# bluebox.net
KiCad netlist of a schematic drawn in EAGLE
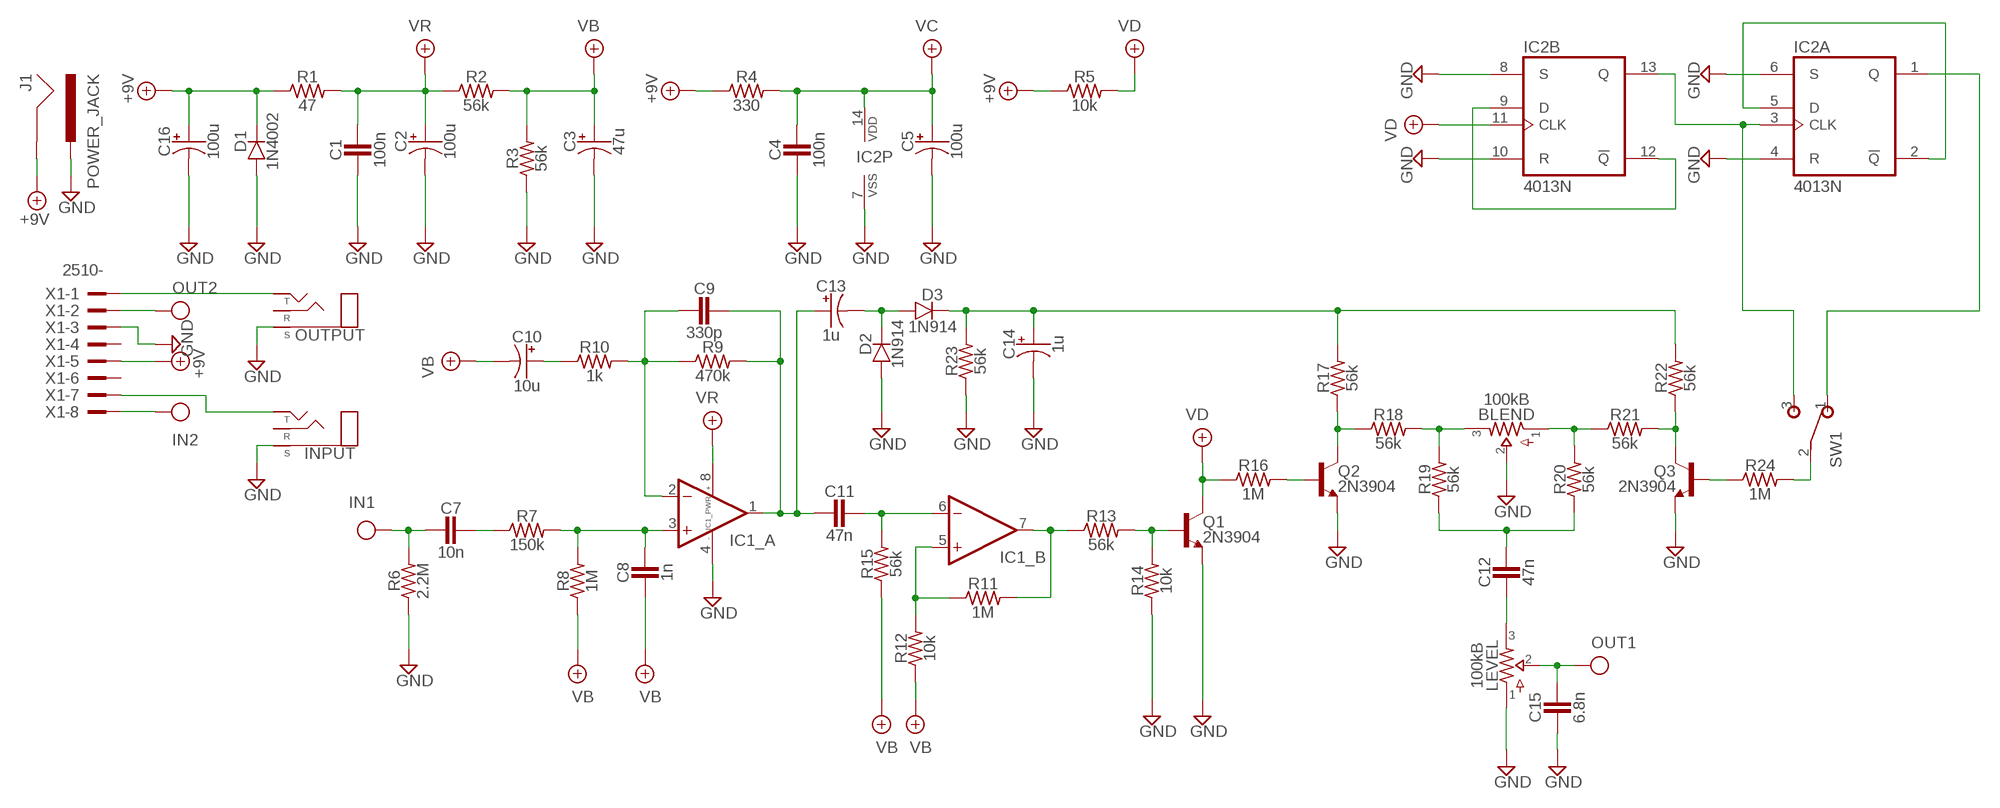
[diagram p0: schematic, sheet 1]

(export (version "E")
  (design (tool "Eeschema 10.0.6"))
  (components
    (comp (ref "BLEND")
      (value "100kB")
      (footprint "eagle-import:16MM")
      (libsource (lib "eagle-import") (part "POTS16MM"))
    )
    (comp (ref "C1")
      (value "100n")
      (footprint "eagle-import:050X030_025_2")
      (libsource (lib "eagle-import") (part "CER/FILM2"))
    )
    (comp (ref "C2")
      (value "100u")
      (footprint "eagle-import:050_020")
      (libsource (lib "eagle-import") (part "0500"))
    )
    (comp (ref "C3")
      (value "47u")
      (footprint "eagle-import:050_020")
      (libsource (lib "eagle-import") (part "0500"))
    )
    (comp (ref "C4")
      (value "100n")
      (footprint "eagle-import:050X030_025_2")
      (libsource (lib "eagle-import") (part "CER/FILM2"))
    )
    (comp (ref "C5")
      (value "100u")
      (footprint "eagle-import:050_020")
      (libsource (lib "eagle-import") (part "0500"))
    )
    (comp (ref "C7")
      (value "10n")
      (footprint "eagle-import:BOX_SMALL")
      (libsource (lib "eagle-import") (part "CER/FILMBOX.1"))
    )
    (comp (ref "C8")
      (value "1n")
      (footprint "eagle-import:BOX_SMALL")
      (libsource (lib "eagle-import") (part "CER/FILMBOX.1"))
    )
    (comp (ref "C9")
      (value "330p")
      (footprint "eagle-import:050X030_025_2")
      (libsource (lib "eagle-import") (part "CER/FILM2"))
    )
    (comp (ref "C10")
      (value "10u")
      (footprint "eagle-import:050_020")
      (libsource (lib "eagle-import") (part "0500"))
    )
    (comp (ref "C11")
      (value "47n")
      (footprint "eagle-import:BOX_SMALL")
      (libsource (lib "eagle-import") (part "CER/FILMBOX.1"))
    )
    (comp (ref "C12")
      (value "47n")
      (footprint "eagle-import:BOX_SMALL")
      (libsource (lib "eagle-import") (part "CER/FILMBOX.1"))
    )
    (comp (ref "C13")
      (value "1u")
      (footprint "eagle-import:040_020")
      (libsource (lib "eagle-import") (part "0400"))
    )
    (comp (ref "C14")
      (value "1u")
      (footprint "eagle-import:040_020")
      (libsource (lib "eagle-import") (part "0400"))
    )
    (comp (ref "C15")
      (value "6.8n")
      (footprint "eagle-import:BOX_SMALL")
      (libsource (lib "eagle-import") (part "CER/FILMBOX.1"))
    )
    (comp (ref "C16")
      (value "100u")
      (footprint "eagle-import:050_020")
      (libsource (lib "eagle-import") (part "0500"))
    )
    (comp (ref "D1")
      (value "1N4002")
      (footprint "eagle-import:DO41-2")
      (libsource (lib "eagle-import") (part "DO41.2"))
    )
    (comp (ref "D2")
      (value "1N914")
      (footprint "eagle-import:DO35-2")
      (libsource (lib "eagle-import") (part "DO35.2"))
    )
    (comp (ref "D3")
      (value "1N914")
      (footprint "eagle-import:DO35-2")
      (libsource (lib "eagle-import") (part "DO35.2"))
    )
    (comp (ref "IC1")
      (value "DUALTH")
      (footprint "eagle-import:DIL0")
      (libsource (lib "eagle-import") (part "DUALTH"))
    )
    (comp (ref "IC2")
      (value "4013N")
      (footprint "eagle-import:DIL14")
      (libsource (lib "eagle-import") (part "4013N"))
    )
    (comp (ref "INPUT")
      (value "STEREONMJ")
      (footprint "eagle-import:NMJ6HCD2")
      (libsource (lib "eagle-import") (part "STEREONMJ"))
    )
    (comp (ref "J1")
      (value "POWER_JACK")
      (footprint "eagle-import:POWER_JACK_PTH")
      (libsource (lib "eagle-import") (part "POWER_JACK"))
    )
    (comp (ref "LEVEL")
      (value "100kB")
      (footprint "eagle-import:16MM")
      (libsource (lib "eagle-import") (part "POTS16MM"))
    )
    (comp (ref "OUTPUT")
      (value "STEREONMJ")
      (footprint "eagle-import:NMJ6HCD2")
      (libsource (lib "eagle-import") (part "STEREONMJ"))
    )
    (comp (ref "Q1")
      (value "2N3904")
      (footprint "eagle-import:TO92-")
      (libsource (lib "eagle-import") (part "2N3904"))
    )
    (comp (ref "Q2")
      (value "2N3904")
      (footprint "eagle-import:TO92-")
      (libsource (lib "eagle-import") (part "2N3904"))
    )
    (comp (ref "Q3")
      (value "2N3904")
      (footprint "eagle-import:TO92-")
      (libsource (lib "eagle-import") (part "2N3904"))
    )
    (comp (ref "R1")
      (value "47")
      (footprint "eagle-import:R0207_3")
      (libsource (lib "eagle-import") (part "R_.3B"))
    )
    (comp (ref "R2")
      (value "56k")
      (footprint "eagle-import:R0207_3")
      (libsource (lib "eagle-import") (part "R_.3B"))
    )
    (comp (ref "R3")
      (value "56k")
      (footprint "eagle-import:R0207_3")
      (libsource (lib "eagle-import") (part "R_.3B"))
    )
    (comp (ref "R4")
      (value "330")
      (footprint "eagle-import:R0207_3")
      (libsource (lib "eagle-import") (part "R_.3B"))
    )
    (comp (ref "R5")
      (value "10k")
      (footprint "eagle-import:R0207_3")
      (libsource (lib "eagle-import") (part "R_.3B"))
    )
    (comp (ref "R6")
      (value "2.2M")
      (footprint "eagle-import:R0207_3")
      (libsource (lib "eagle-import") (part "R_.3B"))
    )
    (comp (ref "R7")
      (value "150k")
      (footprint "eagle-import:R0207_3")
      (libsource (lib "eagle-import") (part "R_.3B"))
    )
    (comp (ref "R8")
      (value "1M")
      (footprint "eagle-import:R0207_3")
      (libsource (lib "eagle-import") (part "R_.3B"))
    )
    (comp (ref "R9")
      (value "470k")
      (footprint "eagle-import:R0207_3")
      (libsource (lib "eagle-import") (part "R_.3B"))
    )
    (comp (ref "R10")
      (value "1k")
      (footprint "eagle-import:R0207_3")
      (libsource (lib "eagle-import") (part "R_.3B"))
    )
    (comp (ref "R11")
      (value "1M")
      (footprint "eagle-import:R0207_3")
      (libsource (lib "eagle-import") (part "R_.3B"))
    )
    (comp (ref "R12")
      (value "10k")
      (footprint "eagle-import:R0207_3")
      (libsource (lib "eagle-import") (part "R_.3B"))
    )
    (comp (ref "R13")
      (value "56k")
      (footprint "eagle-import:R0207_3")
      (libsource (lib "eagle-import") (part "R_.3B"))
    )
    (comp (ref "R14")
      (value "10k")
      (footprint "eagle-import:R0207_3")
      (libsource (lib "eagle-import") (part "R_.3B"))
    )
    (comp (ref "R15")
      (value "56k")
      (footprint "eagle-import:R0207_3")
      (libsource (lib "eagle-import") (part "R_.3B"))
    )
    (comp (ref "R16")
      (value "1M")
      (footprint "eagle-import:R0207_3")
      (libsource (lib "eagle-import") (part "R_.3B"))
    )
    (comp (ref "R17")
      (value "56k")
      (footprint "eagle-import:R0207_3")
      (libsource (lib "eagle-import") (part "R_.3B"))
    )
    (comp (ref "R18")
      (value "56k")
      (footprint "eagle-import:R0207_3")
      (libsource (lib "eagle-import") (part "R_.3B"))
    )
    (comp (ref "R19")
      (value "56k")
      (footprint "eagle-import:R0207_3")
      (libsource (lib "eagle-import") (part "R_.3B"))
    )
    (comp (ref "R20")
      (value "56k")
      (footprint "eagle-import:R0207_3")
      (libsource (lib "eagle-import") (part "R_.3B"))
    )
    (comp (ref "R21")
      (value "56k")
      (footprint "eagle-import:R0207_3")
      (libsource (lib "eagle-import") (part "R_.3B"))
    )
    (comp (ref "R22")
      (value "56k")
      (footprint "eagle-import:R0207_3")
      (libsource (lib "eagle-import") (part "R_.3B"))
    )
    (comp (ref "R23")
      (value "56k")
      (footprint "eagle-import:R0207_3")
      (libsource (lib "eagle-import") (part "R_.3B"))
    )
    (comp (ref "R24")
      (value "1M")
      (footprint "eagle-import:R0207_3")
      (libsource (lib "eagle-import") (part "R_.3B"))
    )
    (comp (ref "SW1")
      (value "SPDTPIN_MOUNT")
      (footprint "eagle-import:1MS1T1B1C0M2QE")
      (libsource (lib "eagle-import") (part "SPDTPIN_MOUNT"))
    )
    (comp (ref "X1")
      (value "2510-")
      (footprint "eagle-import:PAK100_2500-10")
      (fields (field (name "MF") "3M") (field (name "MPN") "2510-6002UB"))
      (libsource (lib "eagle-import") (part "2510-"))
    )
  )
  (nets
    (net (code "1") (name "+9V") (class "Default")
      (node (ref "C16") (pin "+") (pinfunction "+_+") (pintype "passive"))
      (node (ref "D1") (pin "C") (pinfunction "C_C") (pintype "passive"))
      (node (ref "J1") (pin "GND") (pinfunction "GND_GND") (pintype "bidirectional"))
      (node (ref "R1") (pin "1") (pinfunction "1_1") (pintype "passive"))
      (node (ref "R4") (pin "1") (pinfunction "1_1") (pintype "passive"))
      (node (ref "R5") (pin "1") (pinfunction "1_1") (pintype "passive"))
      (node (ref "X1") (pin "5") (pinfunction "KL_5") (pintype "passive"))
    )
    (net (code "2") (name "GND") (class "Default")
      (node (ref "BLEND") (pin "2") (pinfunction "2_2") (pintype "passive"))
      (node (ref "C1") (pin "2") (pinfunction "2_2") (pintype "passive"))
      (node (ref "C14") (pin "-") (pinfunction "-_-") (pintype "passive"))
      (node (ref "C15") (pin "2") (pinfunction "2_2") (pintype "passive"))
      (node (ref "C16") (pin "-") (pinfunction "-_-") (pintype "passive"))
      (node (ref "C2") (pin "-") (pinfunction "-_-") (pintype "passive"))
      (node (ref "C3") (pin "-") (pinfunction "-_-") (pintype "passive"))
      (node (ref "C4") (pin "2") (pinfunction "2_2") (pintype "passive"))
      (node (ref "C5") (pin "-") (pinfunction "-_-") (pintype "passive"))
      (node (ref "D1") (pin "A") (pinfunction "A_A") (pintype "passive"))
      (node (ref "D2") (pin "A") (pinfunction "A_A") (pintype "passive"))
      (node (ref "IC1") (pin "4") (pinfunction "V-_4") (pintype "power_in"))
      (node (ref "IC2") (pin "10") (pinfunction "R_10") (pintype "input"))
      (node (ref "IC2") (pin "4") (pinfunction "R_4") (pintype "input"))
      (node (ref "IC2") (pin "6") (pinfunction "S_6") (pintype "input"))
      (node (ref "IC2") (pin "7") (pinfunction "VSS_7") (pintype "power_in"))
      (node (ref "IC2") (pin "8") (pinfunction "S_8") (pintype "input"))
      (node (ref "INPUT") (pin "S") (pinfunction "S_S") (pintype "passive"))
      (node (ref "J1") (pin "PWR") (pinfunction "PWR_PWR") (pintype "bidirectional"))
      (node (ref "LEVEL") (pin "1") (pinfunction "1_1") (pintype "passive"))
      (node (ref "OUTPUT") (pin "S") (pinfunction "S_S") (pintype "passive"))
      (node (ref "Q1") (pin "3") (pinfunction "E_3") (pintype "passive"))
      (node (ref "Q2") (pin "3") (pinfunction "E_3") (pintype "passive"))
      (node (ref "Q3") (pin "3") (pinfunction "E_3") (pintype "passive"))
      (node (ref "R14") (pin "1") (pinfunction "1_1") (pintype "passive"))
      (node (ref "R23") (pin "1") (pinfunction "1_1") (pintype "passive"))
      (node (ref "R3") (pin "1") (pinfunction "1_1") (pintype "passive"))
      (node (ref "R6") (pin "1") (pinfunction "1_1") (pintype "passive"))
      (node (ref "X1") (pin "3") (pinfunction "KL_3") (pintype "passive"))
    )
    (net (code "3") (name "IN") (class "Default")
      (node (ref "C7") (pin "2") (pinfunction "2_2") (pintype "passive"))
      (node (ref "R6") (pin "2") (pinfunction "2_2") (pintype "passive"))
      (node (ref "X1") (pin "8") (pinfunction "KL_8") (pintype "passive"))
    )
    (net (code "4") (name "Net-(BLEND-Pad1)") (class "Default")
      (node (ref "BLEND") (pin "1") (pinfunction "1_1") (pintype "passive"))
      (node (ref "R20") (pin "2") (pinfunction "2_2") (pintype "passive"))
      (node (ref "R21") (pin "1") (pinfunction "1_1") (pintype "passive"))
    )
    (net (code "5") (name "Net-(BLEND-Pad3)") (class "Default")
      (node (ref "BLEND") (pin "3") (pinfunction "3_3") (pintype "passive"))
      (node (ref "R18") (pin "2") (pinfunction "2_2") (pintype "passive"))
      (node (ref "R19") (pin "2") (pinfunction "2_2") (pintype "passive"))
    )
    (net (code "6") (name "Net-(C7-Pad1)") (class "Default")
      (node (ref "C7") (pin "1") (pinfunction "1_1") (pintype "passive"))
      (node (ref "R7") (pin "1") (pinfunction "1_1") (pintype "passive"))
    )
    (net (code "7") (name "Net-(C10-Pad+)") (class "Default")
      (node (ref "C10") (pin "+") (pinfunction "+_+") (pintype "passive"))
      (node (ref "R10") (pin "1") (pinfunction "1_1") (pintype "passive"))
    )
    (net (code "8") (name "Net-(C12-Pad1)") (class "Default")
      (node (ref "C12") (pin "1") (pinfunction "1_1") (pintype "passive"))
      (node (ref "R19") (pin "1") (pinfunction "1_1") (pintype "passive"))
      (node (ref "R20") (pin "1") (pinfunction "1_1") (pintype "passive"))
    )
    (net (code "9") (name "Net-(C12-Pad2)") (class "Default")
      (node (ref "C12") (pin "2") (pinfunction "2_2") (pintype "passive"))
      (node (ref "LEVEL") (pin "3") (pinfunction "3_3") (pintype "passive"))
    )
    (net (code "10") (name "Net-(C13-Pad-)") (class "Default")
      (node (ref "C13") (pin "-") (pinfunction "-_-") (pintype "passive"))
      (node (ref "D2") (pin "C") (pinfunction "C_C") (pintype "passive"))
      (node (ref "D3") (pin "A") (pinfunction "A_A") (pintype "passive"))
    )
    (net (code "11") (name "Net-(C14-Pad+)") (class "Default")
      (node (ref "C14") (pin "+") (pinfunction "+_+") (pintype "passive"))
      (node (ref "D3") (pin "C") (pinfunction "C_C") (pintype "passive"))
      (node (ref "R17") (pin "2") (pinfunction "2_2") (pintype "passive"))
      (node (ref "R22") (pin "2") (pinfunction "2_2") (pintype "passive"))
      (node (ref "R23") (pin "2") (pinfunction "2_2") (pintype "passive"))
    )
    (net (code "12") (name "Net-(IC1A-+IN)") (class "Default")
      (node (ref "C8") (pin "1") (pinfunction "1_1") (pintype "passive"))
      (node (ref "IC1") (pin "3") (pinfunction "+IN_3") (pintype "input"))
      (node (ref "R7") (pin "2") (pinfunction "2_2") (pintype "passive"))
      (node (ref "R8") (pin "2") (pinfunction "2_2") (pintype "passive"))
    )
    (net (code "13") (name "Net-(IC1A--IN)") (class "Default")
      (node (ref "C9") (pin "2") (pinfunction "2_2") (pintype "passive"))
      (node (ref "IC1") (pin "2") (pinfunction "-IN_2") (pintype "input"))
      (node (ref "R10") (pin "2") (pinfunction "2_2") (pintype "passive"))
      (node (ref "R9") (pin "1") (pinfunction "1_1") (pintype "passive"))
    )
    (net (code "14") (name "Net-(IC1A-OUT)") (class "Default")
      (node (ref "C11") (pin "2") (pinfunction "2_2") (pintype "passive"))
      (node (ref "C13") (pin "+") (pinfunction "+_+") (pintype "passive"))
      (node (ref "C9") (pin "1") (pinfunction "1_1") (pintype "passive"))
      (node (ref "IC1") (pin "1") (pinfunction "OUT_1") (pintype "output"))
      (node (ref "R9") (pin "2") (pinfunction "2_2") (pintype "passive"))
    )
    (net (code "15") (name "Net-(IC1B-+IN)") (class "Default")
      (node (ref "IC1") (pin "5") (pinfunction "+IN_5") (pintype "input"))
      (node (ref "R11") (pin "1") (pinfunction "1_1") (pintype "passive"))
      (node (ref "R12") (pin "2") (pinfunction "2_2") (pintype "passive"))
    )
    (net (code "16") (name "Net-(IC1B--IN)") (class "Default")
      (node (ref "C11") (pin "1") (pinfunction "1_1") (pintype "passive"))
      (node (ref "IC1") (pin "6") (pinfunction "-IN_6") (pintype "input"))
      (node (ref "R15") (pin "2") (pinfunction "2_2") (pintype "passive"))
    )
    (net (code "17") (name "Net-(IC1B-OUT)") (class "Default")
      (node (ref "IC1") (pin "7") (pinfunction "OUT_7") (pintype "output"))
      (node (ref "R11") (pin "2") (pinfunction "2_2") (pintype "passive"))
      (node (ref "R13") (pin "1") (pinfunction "1_1") (pintype "passive"))
    )
    (net (code "18") (name "Net-(IC2A-CLK)") (class "Default")
      (node (ref "IC2") (pin "13") (pinfunction "Q_13") (pintype "output"))
      (node (ref "IC2") (pin "3") (pinfunction "CLK_3") (pintype "input"))
      (node (ref "SW1") (pin "3") (pinfunction "S_3") (pintype "passive"))
    )
    (net (code "19") (name "Net-(IC2A-D)") (class "Default")
      (node (ref "IC2") (pin "2") (pinfunction "~{Q}_2") (pintype "output"))
      (node (ref "IC2") (pin "5") (pinfunction "D_5") (pintype "input"))
    )
    (net (code "20") (name "Net-(IC2A-Q)") (class "Default")
      (node (ref "IC2") (pin "1") (pinfunction "Q_1") (pintype "output"))
      (node (ref "SW1") (pin "1") (pinfunction "O_1") (pintype "passive"))
    )
    (net (code "21") (name "Net-(IC2B-D)") (class "Default")
      (node (ref "IC2") (pin "12") (pinfunction "~{Q}_12") (pintype "output"))
      (node (ref "IC2") (pin "9") (pinfunction "D_9") (pintype "input"))
    )
    (net (code "22") (name "Net-(Q1-B)") (class "Default")
      (node (ref "Q1") (pin "2") (pinfunction "B_2") (pintype "passive"))
      (node (ref "R13") (pin "2") (pinfunction "2_2") (pintype "passive"))
      (node (ref "R14") (pin "2") (pinfunction "2_2") (pintype "passive"))
    )
    (net (code "23") (name "Net-(Q2-B)") (class "Default")
      (node (ref "Q2") (pin "2") (pinfunction "B_2") (pintype "passive"))
      (node (ref "R16") (pin "2") (pinfunction "2_2") (pintype "passive"))
    )
    (net (code "24") (name "Net-(Q2-C)") (class "Default")
      (node (ref "Q2") (pin "1") (pinfunction "C_1") (pintype "passive"))
      (node (ref "R17") (pin "1") (pinfunction "1_1") (pintype "passive"))
      (node (ref "R18") (pin "1") (pinfunction "1_1") (pintype "passive"))
    )
    (net (code "25") (name "Net-(Q3-B)") (class "Default")
      (node (ref "Q3") (pin "2") (pinfunction "B_2") (pintype "passive"))
      (node (ref "R24") (pin "1") (pinfunction "1_1") (pintype "passive"))
    )
    (net (code "26") (name "Net-(Q3-C)") (class "Default")
      (node (ref "Q3") (pin "1") (pinfunction "C_1") (pintype "passive"))
      (node (ref "R21") (pin "2") (pinfunction "2_2") (pintype "passive"))
      (node (ref "R22") (pin "1") (pinfunction "1_1") (pintype "passive"))
    )
    (net (code "27") (name "Net-(SW1-P)") (class "Default")
      (node (ref "R24") (pin "2") (pinfunction "2_2") (pintype "passive"))
      (node (ref "SW1") (pin "2") (pinfunction "P_2") (pintype "passive"))
    )
    (net (code "28") (name "Net-(X1A-KL)") (class "Default")
      (node (ref "OUTPUT") (pin "T") (pinfunction "T_T") (pintype "passive"))
      (node (ref "X1") (pin "1") (pinfunction "KL_1") (pintype "passive"))
    )
    (net (code "29") (name "Net-(X1G-KL)") (class "Default")
      (node (ref "INPUT") (pin "T") (pinfunction "T_T") (pintype "passive"))
      (node (ref "X1") (pin "7") (pinfunction "KL_7") (pintype "passive"))
    )
    (net (code "30") (name "OUT") (class "Default")
      (node (ref "C15") (pin "1") (pinfunction "1_1") (pintype "passive"))
      (node (ref "LEVEL") (pin "2") (pinfunction "2_2") (pintype "passive"))
      (node (ref "X1") (pin "2") (pinfunction "KL_2") (pintype "passive"))
    )
    (net (code "31") (name "VB") (class "Default")
      (node (ref "C10") (pin "-") (pinfunction "-_-") (pintype "passive"))
      (node (ref "C3") (pin "+") (pinfunction "+_+") (pintype "passive"))
      (node (ref "C8") (pin "2") (pinfunction "2_2") (pintype "passive"))
      (node (ref "R12") (pin "1") (pinfunction "1_1") (pintype "passive"))
      (node (ref "R15") (pin "1") (pinfunction "1_1") (pintype "passive"))
      (node (ref "R2") (pin "2") (pinfunction "2_2") (pintype "passive"))
      (node (ref "R3") (pin "2") (pinfunction "2_2") (pintype "passive"))
      (node (ref "R8") (pin "1") (pinfunction "1_1") (pintype "passive"))
    )
    (net (code "32") (name "VC") (class "Default")
      (node (ref "C4") (pin "1") (pinfunction "1_1") (pintype "passive"))
      (node (ref "C5") (pin "+") (pinfunction "+_+") (pintype "passive"))
      (node (ref "IC2") (pin "14") (pinfunction "VDD_14") (pintype "power_in"))
      (node (ref "R4") (pin "2") (pinfunction "2_2") (pintype "passive"))
    )
    (net (code "33") (name "VD") (class "Default")
      (node (ref "IC2") (pin "11") (pinfunction "CLK_11") (pintype "input"))
      (node (ref "Q1") (pin "1") (pinfunction "C_1") (pintype "passive"))
      (node (ref "R16") (pin "1") (pinfunction "1_1") (pintype "passive"))
      (node (ref "R5") (pin "2") (pinfunction "2_2") (pintype "passive"))
    )
    (net (code "34") (name "VR") (class "Default")
      (node (ref "C1") (pin "1") (pinfunction "1_1") (pintype "passive"))
      (node (ref "C2") (pin "+") (pinfunction "+_+") (pintype "passive"))
      (node (ref "IC1") (pin "8") (pinfunction "V+_8") (pintype "power_in"))
      (node (ref "R1") (pin "2") (pinfunction "2_2") (pintype "passive"))
      (node (ref "R2") (pin "1") (pinfunction "1_1") (pintype "passive"))
    )
    (net (code "35") (name "unconnected-(INPUT-PadR)") (class "Default")
      (node (ref "INPUT") (pin "R") (pinfunction "R_R") (pintype "passive"))
    )
    (net (code "36") (name "unconnected-(OUTPUT-PadR)") (class "Default")
      (node (ref "OUTPUT") (pin "R") (pinfunction "R_R") (pintype "passive"))
    )
    (net (code "37") (name "unconnected-(X1D-KL-Pad4)") (class "Default")
      (node (ref "X1") (pin "4") (pinfunction "KL_4") (pintype "passive"))
    )
    (net (code "38") (name "unconnected-(X1F-KL-Pad6)") (class "Default")
      (node (ref "X1") (pin "6") (pinfunction "KL_6") (pintype "passive"))
    )
  )
)
